# 01_Power_IN-CUAVBIN.net
KiCad netlist of a schematic drawn in Altium Designer
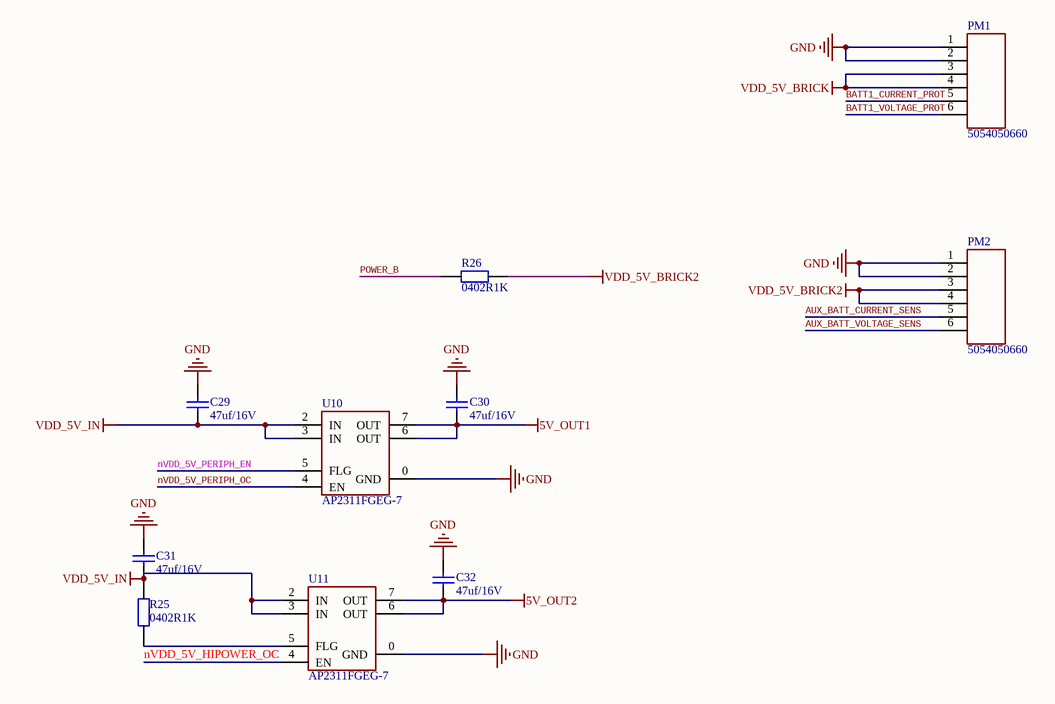
[diagram p0: 01_Power_IN-CUAVBIN.SchDoc]

(export (version "E")
  (design (tool "Eeschema 10.0.6"))
  (components
    (comp (ref "C29")
      (value "47uf/16V")
      (description "Capacitor")
      (libsource (lib "Miscellaneous Devices") (part "Cap"))
    )
    (comp (ref "C30")
      (value "47uf/16V")
      (description "Capacitor")
      (libsource (lib "Miscellaneous Devices") (part "Cap"))
    )
    (comp (ref "C31")
      (value "47uf/16V")
      (description "Capacitor")
      (libsource (lib "Miscellaneous Devices") (part "Cap"))
    )
    (comp (ref "C32")
      (value "47uf/16V")
      (description "Capacitor")
      (libsource (lib "Miscellaneous Devices") (part "Cap"))
    )
    (comp (ref "PM1")
      (value "5054050660")
      (footprint "5054050660")
      (libsource (lib "CUAV") (part "5054050660"))
    )
    (comp (ref "PM2")
      (value "5054050660")
      (footprint "5054050660")
      (libsource (lib "CUAV") (part "5054050660"))
    )
    (comp (ref "R25")
      (value "0402R1K")
      (footprint "0402R")
      (description "0402R1K 1%")
      (libsource (lib "") (part "0402R1K_1"))
    )
    (comp (ref "R26")
      (value "0402R1K")
      (footprint "0402R")
      (description "0402R1K 1%")
      (libsource (lib "CUAV") (part "0402R1K"))
    )
    (comp (ref "U10")
      (value "AP2311FGEG-7")
      (footprint "QFN8_0.65")
      (libsource (lib "CUAV") (part "AP2311FGEG-7"))
    )
    (comp (ref "U11")
      (value "AP2311FGEG-7")
      (footprint "QFN8_0.65")
      (libsource (lib "CUAV") (part "AP2311FGEG-7"))
    )
  )
  (nets
    (net (code "1") (name "/AUX_BATT_CURRENT_SENS") (class "Default")
      (node (ref "PM2") (pin "5") (pintype "passive"))
    )
    (net (code "2") (name "/AUX_BATT_VOLTAGE_SENS") (class "Default")
      (node (ref "PM2") (pin "6") (pintype "passive"))
    )
    (net (code "3") (name "/BATT1_CURRENT_PROT") (class "Default")
      (node (ref "PM1") (pin "5") (pintype "passive"))
    )
    (net (code "4") (name "/BATT1_VOLTAGE_PROT") (class "Default")
      (node (ref "PM1") (pin "6") (pintype "passive"))
    )
    (net (code "5") (name "/POWER_B") (class "Default") (node (ref "R26") (pin "1") (pintype "passive")))
    (net (code "6") (name "/nVDD_5V_HIPOWER_OC") (class "Default")
      (node (ref "U11") (pin "4") (pinfunction "EN_4") (pintype "passive"))
    )
    (net (code "7") (name "/nVDD_5V_PERIPH_EN") (class "Default")
      (node (ref "U10") (pin "5") (pinfunction "FLG_5") (pintype "passive"))
    )
    (net (code "8") (name "/nVDD_5V_PERIPH_OC") (class "Default")
      (node (ref "U10") (pin "4") (pinfunction "EN_4") (pintype "passive"))
    )
    (net (code "9") (name "5V_OUT1") (class "Default")
      (node (ref "C30") (pin "1") (pinfunction "1_1") (pintype "passive"))
      (node (ref "U10") (pin "6") (pinfunction "OUT_6") (pintype "passive"))
      (node (ref "U10") (pin "7") (pinfunction "OUT_7") (pintype "passive"))
    )
    (net (code "10") (name "5V_OUT2") (class "Default")
      (node (ref "C32") (pin "1") (pinfunction "1_1") (pintype "passive"))
      (node (ref "U11") (pin "6") (pinfunction "OUT_6") (pintype "passive"))
      (node (ref "U11") (pin "7") (pinfunction "OUT_7") (pintype "passive"))
    )
    (net (code "11") (name "GND") (class "Default")
      (node (ref "C29") (pin "2") (pinfunction "2_2") (pintype "passive"))
      (node (ref "C30") (pin "2") (pinfunction "2_2") (pintype "passive"))
      (node (ref "C31") (pin "2") (pinfunction "2_2") (pintype "passive"))
      (node (ref "C32") (pin "2") (pinfunction "2_2") (pintype "passive"))
      (node (ref "PM1") (pin "1") (pintype "passive"))
      (node (ref "PM1") (pin "2") (pintype "passive"))
      (node (ref "PM2") (pin "1") (pintype "passive"))
      (node (ref "PM2") (pin "2") (pintype "passive"))
      (node (ref "U10") (pin "0") (pinfunction "GND_0") (pintype "passive"))
      (node (ref "U11") (pin "0") (pinfunction "GND_0") (pintype "passive"))
    )
    (net (code "12") (name "Net-(U11-FLG)") (class "Default")
      (node (ref "R25") (pin "1") (pintype "passive"))
      (node (ref "U11") (pin "5") (pinfunction "FLG_5") (pintype "passive"))
    )
    (net (code "13") (name "VDD_5V_BRICK") (class "Default")
      (node (ref "PM1") (pin "3") (pintype "passive"))
      (node (ref "PM1") (pin "4") (pintype "passive"))
    )
    (net (code "14") (name "VDD_5V_BRICK2") (class "Default")
      (node (ref "PM2") (pin "3") (pintype "passive"))
      (node (ref "PM2") (pin "4") (pintype "passive"))
      (node (ref "R26") (pin "2") (pintype "passive"))
    )
    (net (code "15") (name "VDD_5V_IN") (class "Default")
      (node (ref "C29") (pin "1") (pinfunction "1_1") (pintype "passive"))
      (node (ref "C31") (pin "1") (pinfunction "1_1") (pintype "passive"))
      (node (ref "R25") (pin "2") (pintype "passive"))
      (node (ref "U10") (pin "2") (pinfunction "IN_2") (pintype "passive"))
      (node (ref "U10") (pin "3") (pinfunction "IN_3") (pintype "passive"))
      (node (ref "U11") (pin "2") (pinfunction "IN_2") (pintype "passive"))
      (node (ref "U11") (pin "3") (pinfunction "IN_3") (pintype "passive"))
    )
  )
)
